# ArduinoHub08Shield.net
KiCad netlist of a schematic drawn in EAGLE
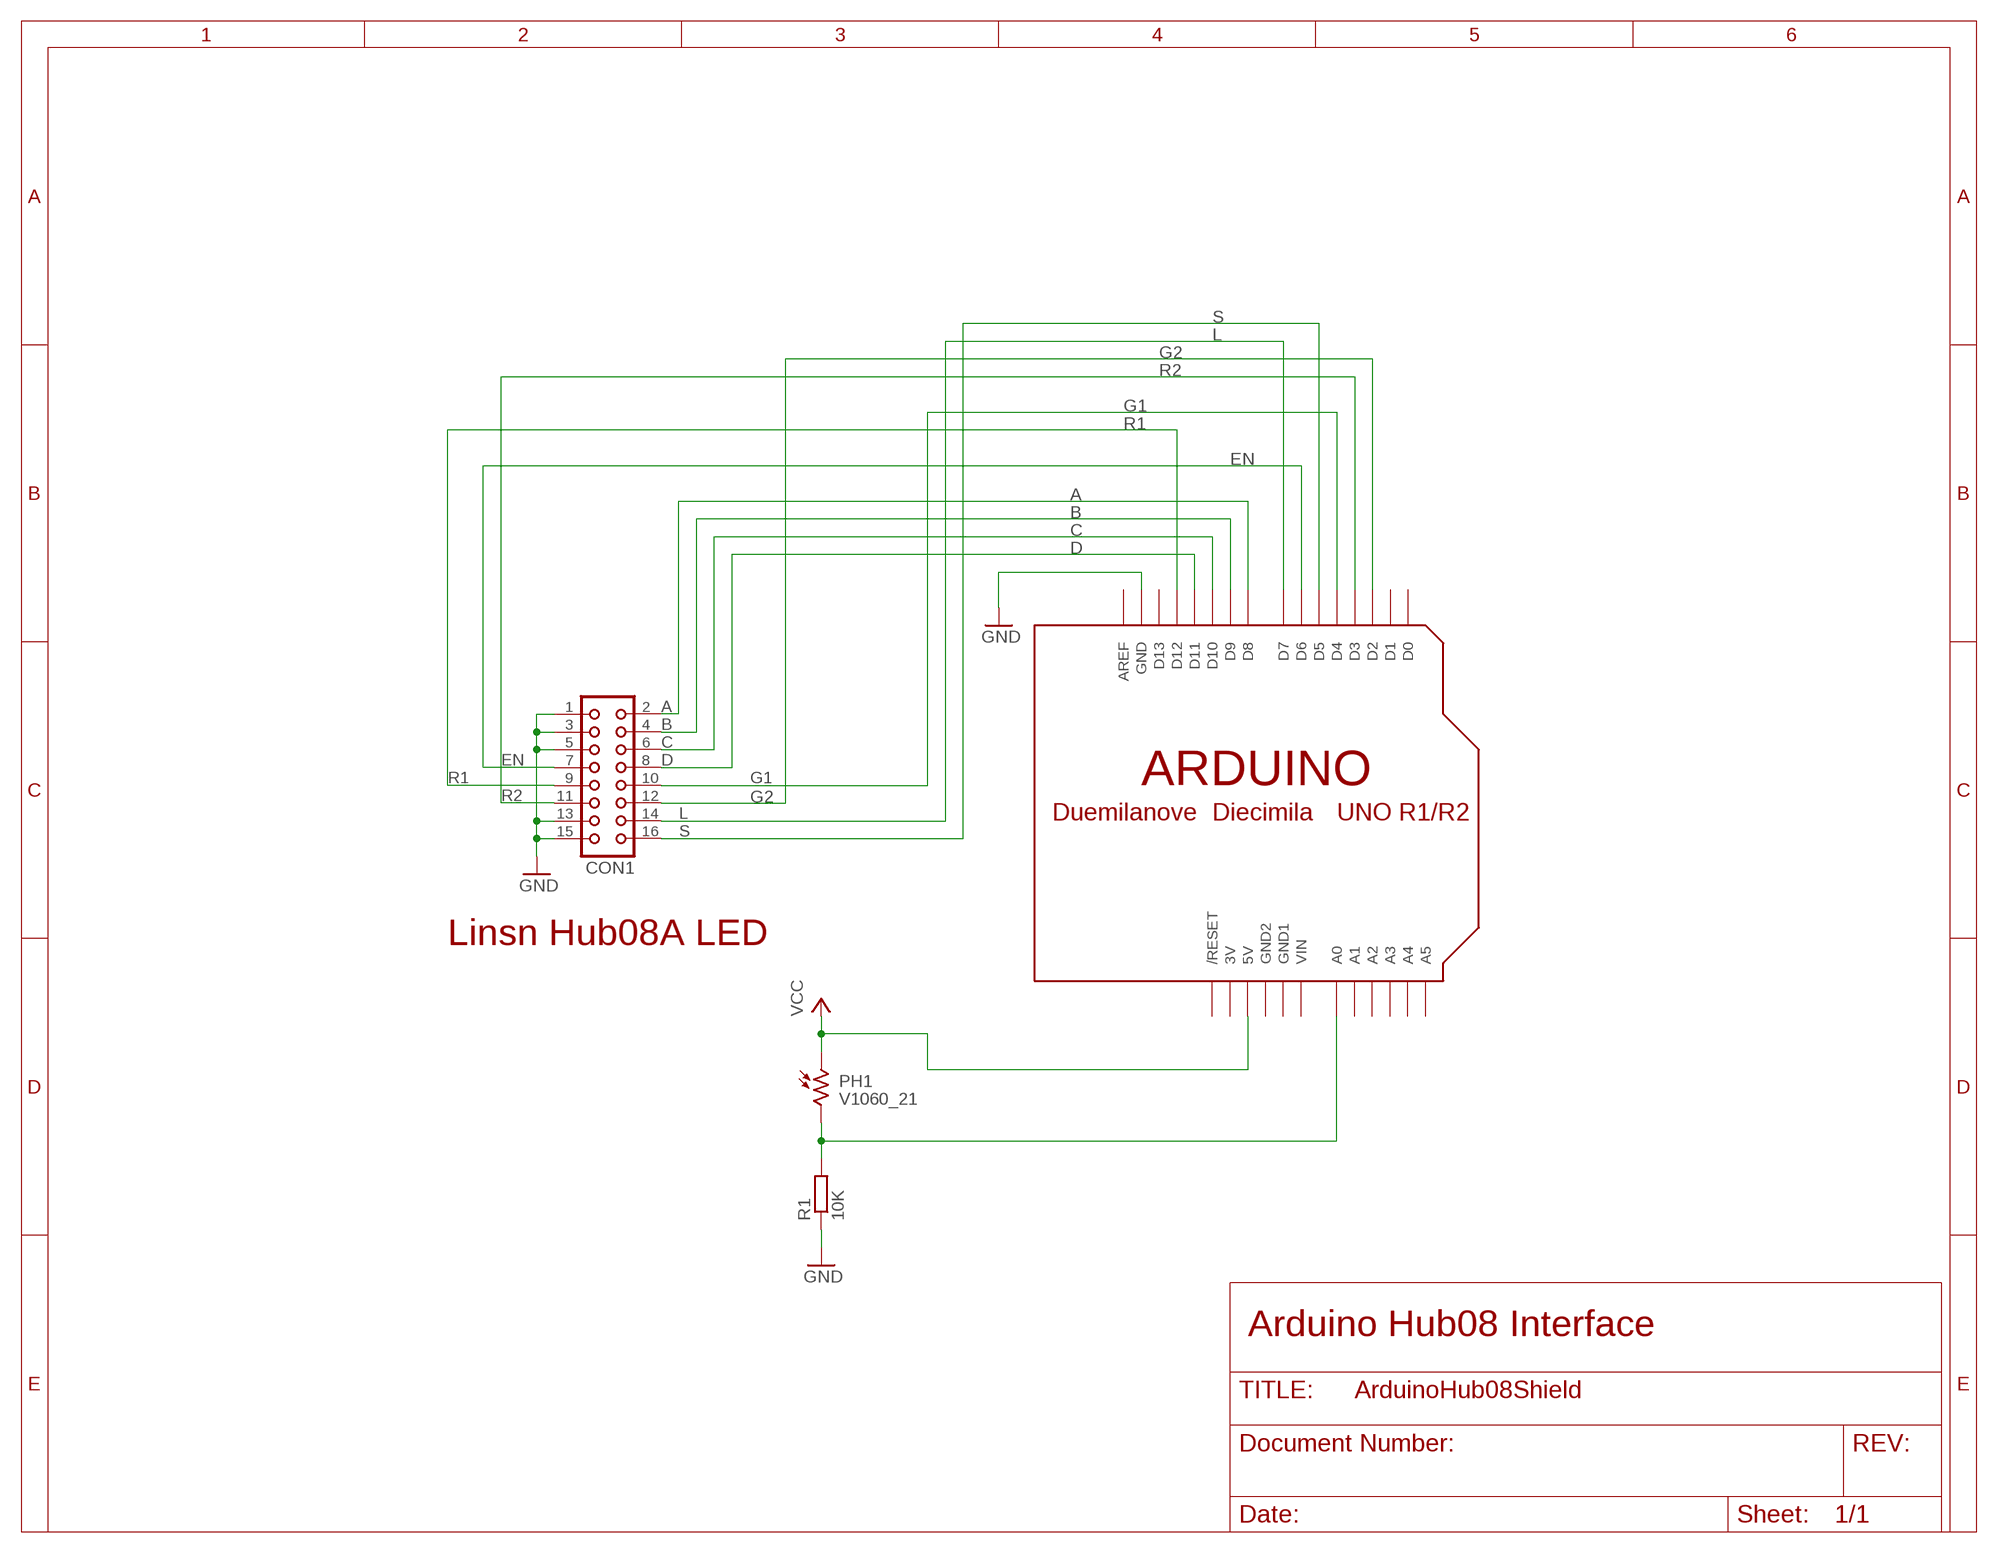
[diagram p0: schematic, sheet 1]

(export (version "E")
  (design (tool "Eeschema 10.0.6"))
  (components
    (comp (ref "CON1")
      (value "CON16")
      (footprint "eagle-import:CON16")
      (libsource (lib "eagle-import") (part "CON16"))
    )
    (comp (ref "PH1")
      (value "V1060_21")
      (footprint "eagle-import:TO-5_V10")
      (libsource (lib "eagle-import") (part "?1060V_21"))
    )
    (comp (ref "R1")
      (value "10K")
      (footprint "eagle-import:0204_7")
      (libsource (lib "eagle-import") (part "R-EU_0204/7"))
    )
    (comp (ref "U$1")
      (value "ARDUINO-NOHOLE")
      (footprint "eagle-import:ARDUINO-NOHOLE")
      (libsource (lib "eagle-import") (part "ARDUINO-NOHOLE"))
    )
  )
  (nets
    (net (code "1") (name "/3V") (class "Default")
      (node (ref "U$1") (pin "3V") (pinfunction "3V_3V") (pintype "power_in"))
    )
    (net (code "2") (name "/A") (class "Default")
      (node (ref "CON1") (pin "2") (pinfunction "2_2") (pintype "passive"))
      (node (ref "U$1") (pin "D8") (pinfunction "D8_D8") (pintype "bidirectional"))
    )
    (net (code "3") (name "/B") (class "Default")
      (node (ref "CON1") (pin "4") (pinfunction "4_4") (pintype "passive"))
      (node (ref "U$1") (pin "D9") (pinfunction "D9_D9") (pintype "bidirectional"))
    )
    (net (code "4") (name "/C") (class "Default")
      (node (ref "CON1") (pin "6") (pinfunction "6_6") (pintype "passive"))
      (node (ref "U$1") (pin "D10") (pinfunction "D10_D10") (pintype "bidirectional"))
    )
    (net (code "5") (name "/D") (class "Default")
      (node (ref "CON1") (pin "8") (pinfunction "8_8") (pintype "passive"))
      (node (ref "U$1") (pin "D11") (pinfunction "D11_D11") (pintype "bidirectional"))
    )
    (net (code "6") (name "/EN") (class "Default")
      (node (ref "CON1") (pin "7") (pinfunction "7_7") (pintype "passive"))
      (node (ref "U$1") (pin "D6") (pinfunction "D6_D6") (pintype "bidirectional"))
    )
    (net (code "7") (name "/G1") (class "Default")
      (node (ref "CON1") (pin "10") (pinfunction "10_10") (pintype "passive"))
      (node (ref "U$1") (pin "D4") (pinfunction "D4_D4") (pintype "bidirectional"))
    )
    (net (code "8") (name "/G2") (class "Default")
      (node (ref "CON1") (pin "12") (pinfunction "12_12") (pintype "passive"))
      (node (ref "U$1") (pin "D2") (pinfunction "D2_D2") (pintype "bidirectional"))
    )
    (net (code "9") (name "/GND1") (class "Default")
      (node (ref "U$1") (pin "GND1") (pinfunction "GND1_GND1") (pintype "power_in"))
    )
    (net (code "10") (name "/GND2") (class "Default")
      (node (ref "U$1") (pin "GND2") (pinfunction "GND2_GND2") (pintype "power_in"))
    )
    (net (code "11") (name "/L") (class "Default")
      (node (ref "CON1") (pin "14") (pinfunction "14_14") (pintype "passive"))
      (node (ref "U$1") (pin "D7") (pinfunction "D7_D7") (pintype "bidirectional"))
    )
    (net (code "12") (name "/R1") (class "Default")
      (node (ref "CON1") (pin "9") (pinfunction "9_9") (pintype "passive"))
      (node (ref "U$1") (pin "D12") (pinfunction "D12_D12") (pintype "bidirectional"))
    )
    (net (code "13") (name "/R2") (class "Default")
      (node (ref "CON1") (pin "11") (pinfunction "11_11") (pintype "passive"))
      (node (ref "U$1") (pin "D3") (pinfunction "D3_D3") (pintype "bidirectional"))
    )
    (net (code "14") (name "/S") (class "Default")
      (node (ref "CON1") (pin "16") (pinfunction "16_16") (pintype "passive"))
      (node (ref "U$1") (pin "D5") (pinfunction "D5_D5") (pintype "bidirectional"))
    )
    (net (code "15") (name "/VIN") (class "Default")
      (node (ref "U$1") (pin "VIN") (pinfunction "VIN_VIN") (pintype "power_in"))
    )
    (net (code "16") (name "GND") (class "Default")
      (node (ref "CON1") (pin "1") (pinfunction "1_1") (pintype "passive"))
      (node (ref "CON1") (pin "13") (pinfunction "13_13") (pintype "passive"))
      (node (ref "CON1") (pin "15") (pinfunction "15_15") (pintype "passive"))
      (node (ref "CON1") (pin "3") (pinfunction "3_3") (pintype "passive"))
      (node (ref "CON1") (pin "5") (pinfunction "5_5") (pintype "passive"))
      (node (ref "R1") (pin "1") (pinfunction "1_1") (pintype "passive"))
      (node (ref "U$1") (pin "GND") (pinfunction "GND_GND") (pintype "power_in"))
    )
    (net (code "17") (name "Net-(PH1-Pad2)") (class "Default")
      (node (ref "PH1") (pin "2") (pinfunction "2_2") (pintype "passive"))
      (node (ref "R1") (pin "2") (pinfunction "2_2") (pintype "passive"))
      (node (ref "U$1") (pin "A0") (pinfunction "A0_A0") (pintype "bidirectional"))
    )
    (net (code "18") (name "VCC") (class "Default")
      (node (ref "PH1") (pin "1") (pinfunction "1_1") (pintype "passive"))
      (node (ref "U$1") (pin "5V") (pinfunction "5V_5V") (pintype "power_in"))
    )
    (net (code "19") (name "unconnected-(U$1-PadA1)") (class "Default")
      (node (ref "U$1") (pin "A1") (pinfunction "A1_A1") (pintype "bidirectional"))
    )
    (net (code "20") (name "unconnected-(U$1-PadA2)") (class "Default")
      (node (ref "U$1") (pin "A2") (pinfunction "A2_A2") (pintype "bidirectional"))
    )
    (net (code "21") (name "unconnected-(U$1-PadA3)") (class "Default")
      (node (ref "U$1") (pin "A3") (pinfunction "A3_A3") (pintype "bidirectional"))
    )
    (net (code "22") (name "unconnected-(U$1-PadA4)") (class "Default")
      (node (ref "U$1") (pin "A4") (pinfunction "A4_A4") (pintype "bidirectional"))
    )
    (net (code "23") (name "unconnected-(U$1-PadA5)") (class "Default")
      (node (ref "U$1") (pin "A5") (pinfunction "A5_A5") (pintype "bidirectional"))
    )
    (net (code "24") (name "unconnected-(U$1-PadAREF)") (class "Default")
      (node (ref "U$1") (pin "AREF") (pinfunction "AREF_AREF") (pintype "bidirectional"))
    )
    (net (code "25") (name "unconnected-(U$1-PadD0)") (class "Default")
      (node (ref "U$1") (pin "D0") (pinfunction "D0_D0") (pintype "bidirectional"))
    )
    (net (code "26") (name "unconnected-(U$1-PadD1)") (class "Default")
      (node (ref "U$1") (pin "D1") (pinfunction "D1_D1") (pintype "bidirectional"))
    )
    (net (code "27") (name "unconnected-(U$1-PadD13)") (class "Default")
      (node (ref "U$1") (pin "D13") (pinfunction "D13_D13") (pintype "bidirectional"))
    )
    (net (code "28") (name "unconnected-(U$1-{slash}RESET-PadRESET)") (class "Default")
      (node (ref "U$1") (pin "RESET") (pinfunction "/RESET_RESET") (pintype "bidirectional"))
    )
  )
)
